# 01-POWER.net
KiCad netlist of a schematic drawn in Altium Designer
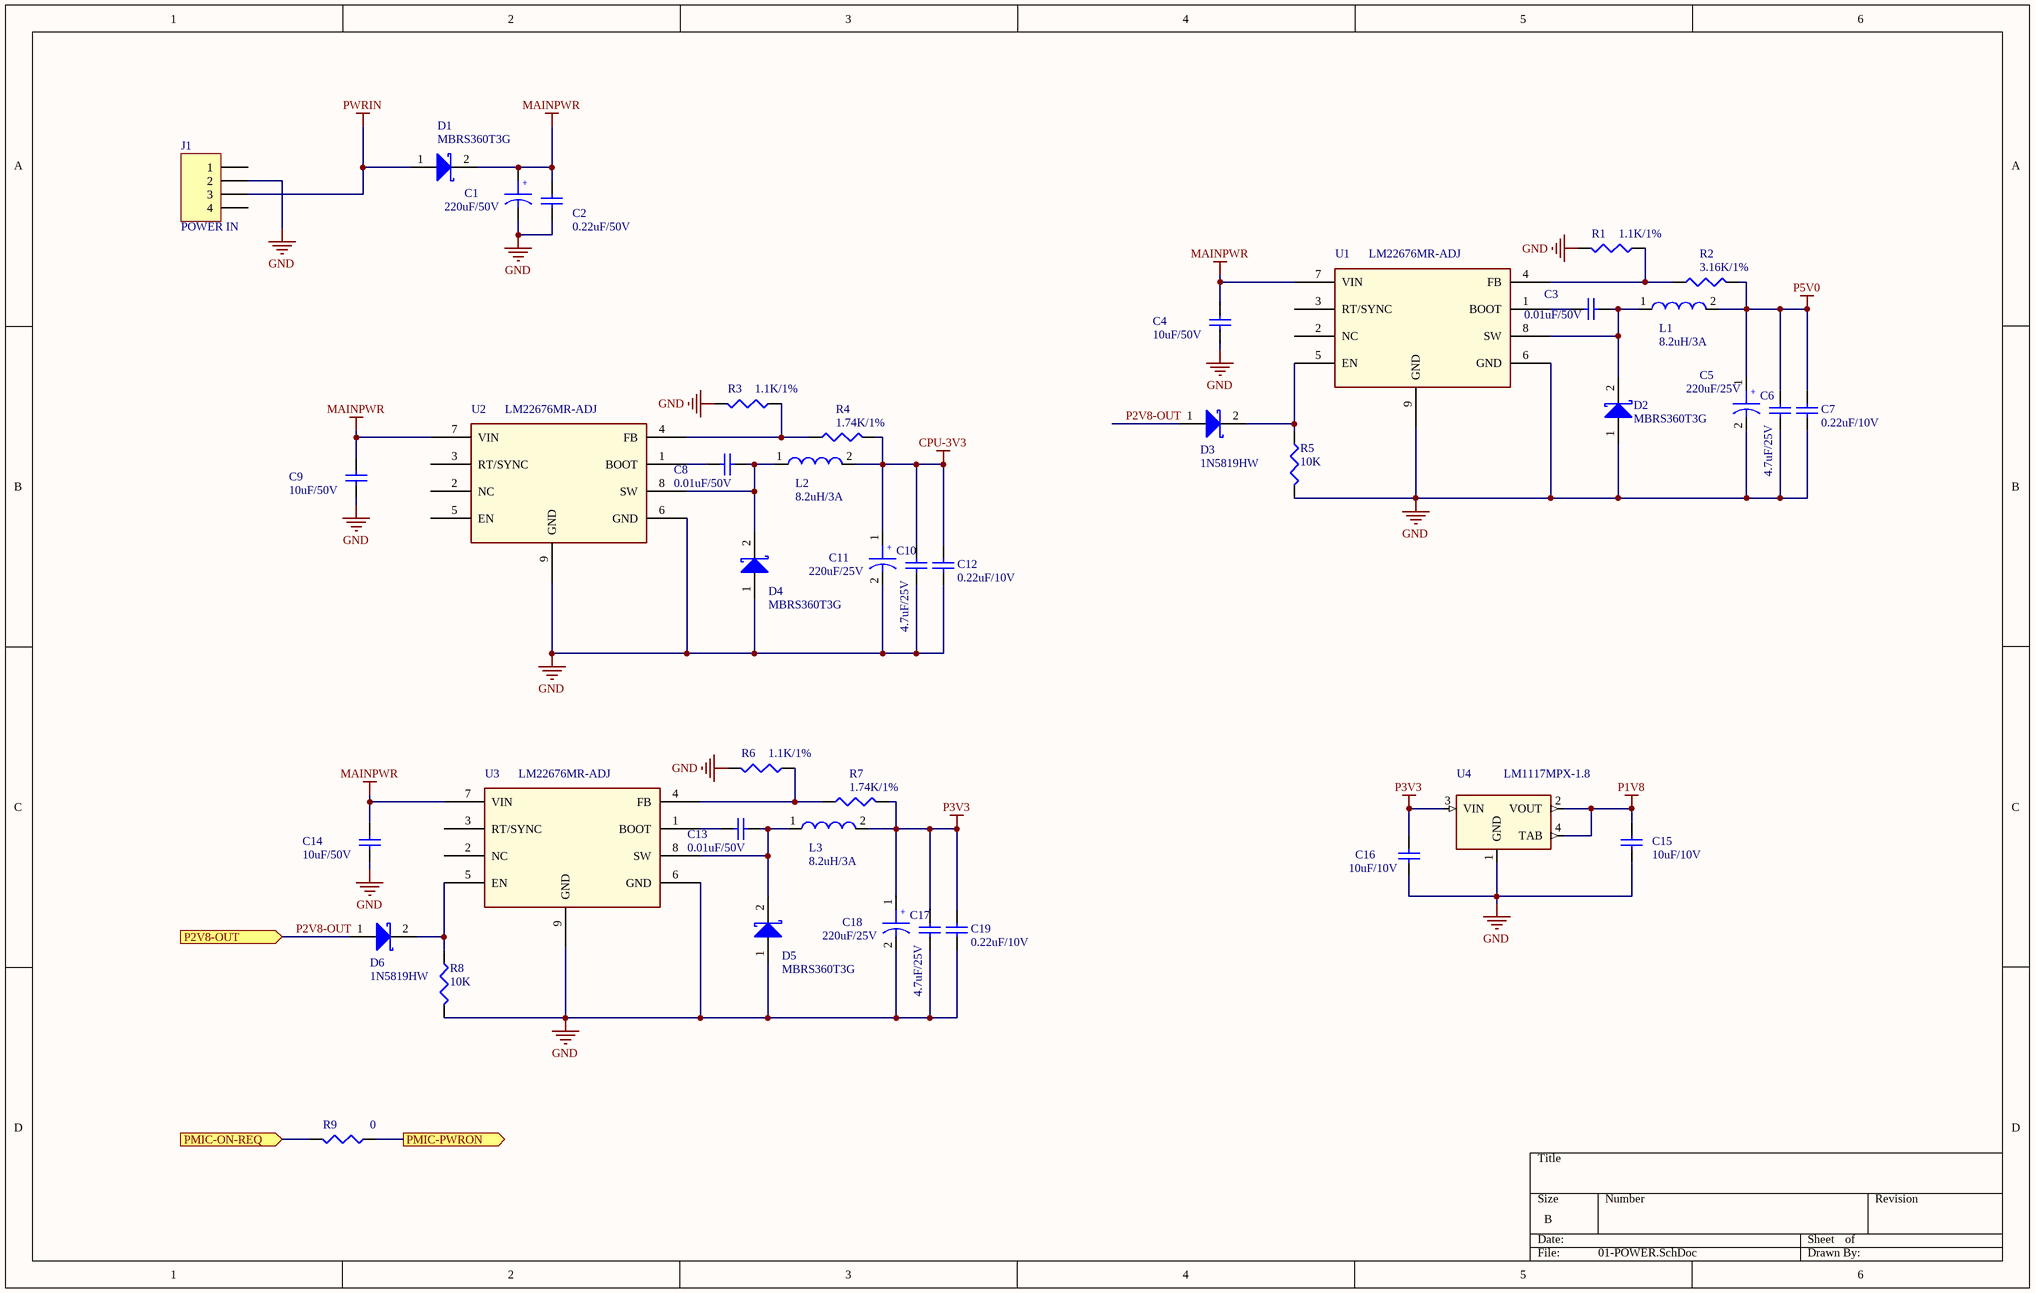
[diagram p0: 01-POWER.SchDoc]

(export (version "E")
  (design (tool "Eeschema 10.0.6"))
  (components
    (comp (ref "C1") (value "220uF/50V") (footprint "DL-10*10.5") (libsource (lib "") (part "CAP WP_1")))
    (comp (ref "C2")
      (value "0.22uF/50V")
      (footprint "0603")
      (description "Capacitor")
      (fields (field (name "PUBLISHER") "Altium Limited"))
      (libsource (lib "Miscellaneous Devices") (part "Cap"))
    )
    (comp (ref "C3")
      (value "0.01uF/50V")
      (footprint "0402")
      (description "Capacitor")
      (fields (field (name "PUBLISHER") "Altium Limited"))
      (libsource (lib "Miscellaneous Devices") (part "Cap"))
    )
    (comp (ref "C4")
      (value "10uF/50V")
      (footprint "1210")
      (description "Capacitor")
      (fields (field (name "PUBLISHER") "Altium Limited"))
      (libsource (lib "Miscellaneous Devices") (part "Cap"))
    )
    (comp (ref "C5") (value "220uF/25V") (footprint "DL-8*10.5") (libsource (lib "*") (part "CAP WP")))
    (comp (ref "C6")
      (value "4.7uF/25V")
      (footprint "0805")
      (description "Capacitor")
      (fields (field (name "PUBLISHER") "Altium Limited"))
      (libsource (lib "Miscellaneous Devices") (part "Cap"))
    )
    (comp (ref "C7")
      (value "0.22uF/10V")
      (footprint "0402")
      (description "Capacitor")
      (fields (field (name "PUBLISHER") "Altium Limited"))
      (libsource (lib "Miscellaneous Devices") (part "Cap"))
    )
    (comp (ref "C8")
      (value "0.01uF/50V")
      (footprint "0402")
      (description "Capacitor")
      (fields (field (name "PUBLISHER") "Altium Limited"))
      (libsource (lib "Miscellaneous Devices") (part "Cap"))
    )
    (comp (ref "C9")
      (value "10uF/50V")
      (footprint "1210")
      (description "Capacitor")
      (fields (field (name "PUBLISHER") "Altium Limited"))
      (libsource (lib "Miscellaneous Devices") (part "Cap"))
    )
    (comp (ref "C10")
      (value "4.7uF/25V")
      (footprint "0805")
      (description "Capacitor")
      (fields (field (name "PUBLISHER") "Altium Limited"))
      (libsource (lib "Miscellaneous Devices") (part "Cap"))
    )
    (comp (ref "C11") (value "220uF/25V") (footprint "DL-8*10.5") (libsource (lib "*") (part "CAP WP")))
    (comp (ref "C12")
      (value "0.22uF/10V")
      (footprint "0402")
      (description "Capacitor")
      (fields (field (name "PUBLISHER") "Altium Limited"))
      (libsource (lib "Miscellaneous Devices") (part "Cap"))
    )
    (comp (ref "C13")
      (value "0.01uF/50V")
      (footprint "0402")
      (description "Capacitor")
      (fields (field (name "PUBLISHER") "Altium Limited"))
      (libsource (lib "Miscellaneous Devices") (part "Cap"))
    )
    (comp (ref "C14")
      (value "10uF/50V")
      (footprint "1210")
      (description "Capacitor")
      (fields (field (name "PUBLISHER") "Altium Limited"))
      (libsource (lib "Miscellaneous Devices") (part "Cap"))
    )
    (comp (ref "C15")
      (value "10uF/10V")
      (footprint "0805")
      (description "Capacitor")
      (fields (field (name "PUBLISHER") "Altium Limited"))
      (libsource (lib "Miscellaneous Devices") (part "Cap"))
    )
    (comp (ref "C16")
      (value "10uF/10V")
      (footprint "0805")
      (description "Capacitor")
      (fields (field (name "PUBLISHER") "Altium Limited"))
      (libsource (lib "Miscellaneous Devices") (part "Cap"))
    )
    (comp (ref "C17")
      (value "4.7uF/25V")
      (footprint "0805")
      (description "Capacitor")
      (fields (field (name "PUBLISHER") "Altium Limited"))
      (libsource (lib "Miscellaneous Devices") (part "Cap"))
    )
    (comp (ref "C18") (value "220uF/25V") (footprint "DL-8*10.5") (libsource (lib "*") (part "CAP WP")))
    (comp (ref "C19")
      (value "0.22uF/10V")
      (footprint "0402")
      (description "Capacitor")
      (fields (field (name "PUBLISHER") "Altium Limited"))
      (libsource (lib "Miscellaneous Devices") (part "Cap"))
    )
    (comp (ref "D1")
      (value "MBRS360T3G")
      (footprint "SMC")
      (description "Schottky Rectifier")
      (libsource (lib "Miscellaneous Devices") (part "Diode 11DQ03"))
    )
    (comp (ref "D2")
      (value "MBRS360T3G")
      (footprint "SMC")
      (description "Schottky Rectifier")
      (libsource (lib "Miscellaneous Devices") (part "Diode 11DQ03"))
    )
    (comp (ref "D3")
      (value "1N5819HW")
      (footprint "1N5819")
      (description "Schottky Rectifier")
      (libsource (lib "Miscellaneous Devices") (part "Diode 11DQ03"))
    )
    (comp (ref "D4")
      (value "MBRS360T3G")
      (footprint "SMC")
      (description "Schottky Rectifier")
      (libsource (lib "Miscellaneous Devices") (part "Diode 11DQ03"))
    )
    (comp (ref "D5")
      (value "MBRS360T3G")
      (footprint "SMC")
      (description "Schottky Rectifier")
      (libsource (lib "Miscellaneous Devices") (part "Diode 11DQ03"))
    )
    (comp (ref "D6")
      (value "1N5819HW")
      (footprint "1N5819")
      (description "Schottky Rectifier")
      (libsource (lib "Miscellaneous Devices") (part "Diode 11DQ03"))
    )
    (comp (ref "J1")
      (value "POWER IN")
      (footprint "5557-4PIN")
      (description "Header, 4-Pin")
      (fields (field (name "PUBLISHER") "Altium Limited"))
      (libsource (lib "Miscellaneous Connectors") (part "Header 4"))
    )
    (comp (ref "L1")
      (value "8.2uH/3A")
      (footprint "IND_10X10")
      (fields (field (name "PART NUMBER") "SH00000AJ00"))
      (libsource (lib "*") (part "4.7UH_CDH2D09BNP-4R7MC_0.7A_20%"))
    )
    (comp (ref "L2")
      (value "8.2uH/3A")
      (footprint "IND_10X10")
      (fields (field (name "PART NUMBER") "SH00000AJ00"))
      (libsource (lib "*") (part "4.7UH_CDH2D09BNP-4R7MC_0.7A_20%"))
    )
    (comp (ref "L3")
      (value "8.2uH/3A")
      (footprint "IND_10X10")
      (fields (field (name "PART NUMBER") "SH00000AJ00"))
      (libsource (lib "*") (part "4.7UH_CDH2D09BNP-4R7MC_0.7A_20%"))
    )
    (comp (ref "R1")
      (value "1.1K/1%")
      (footprint "0402")
      (description "Resistor")
      (fields (field (name "PUBLISHER") "Altium Limited"))
      (libsource (lib "Miscellaneous Devices") (part "Res3"))
    )
    (comp (ref "R2")
      (value "3.16K/1%")
      (footprint "0402")
      (description "Resistor")
      (fields (field (name "PUBLISHER") "Altium Limited"))
      (libsource (lib "Miscellaneous Devices") (part "Res3"))
    )
    (comp (ref "R3")
      (value "1.1K/1%")
      (footprint "0402")
      (description "Resistor")
      (fields (field (name "PUBLISHER") "Altium Limited"))
      (libsource (lib "Miscellaneous Devices") (part "Res3"))
    )
    (comp (ref "R4")
      (value "1.74K/1%")
      (footprint "0402")
      (description "Resistor")
      (fields (field (name "PUBLISHER") "Altium Limited"))
      (libsource (lib "Miscellaneous Devices") (part "Res3"))
    )
    (comp (ref "R5")
      (value "10K")
      (footprint "0402")
      (description "Resistor")
      (fields (field (name "PUBLISHER") "Altium Limited"))
      (libsource (lib "Miscellaneous Devices") (part "Res3"))
    )
    (comp (ref "R6")
      (value "1.1K/1%")
      (footprint "0402")
      (description "Resistor")
      (fields (field (name "PUBLISHER") "Altium Limited"))
      (libsource (lib "Miscellaneous Devices") (part "Res3"))
    )
    (comp (ref "R7")
      (value "1.74K/1%")
      (footprint "0402")
      (description "Resistor")
      (fields (field (name "PUBLISHER") "Altium Limited"))
      (libsource (lib "Miscellaneous Devices") (part "Res3"))
    )
    (comp (ref "R8")
      (value "10K")
      (footprint "0402")
      (description "Resistor")
      (fields (field (name "PUBLISHER") "Altium Limited"))
      (libsource (lib "Miscellaneous Devices") (part "Res3"))
    )
    (comp (ref "R9")
      (value "0")
      (footprint "0402")
      (description "Resistor")
      (fields (field (name "PUBLISHER") "Altium Limited"))
      (libsource (lib "Miscellaneous Devices") (part "Res3"))
    )
    (comp (ref "U1") (value "LM22676MR-ADJ") (libsource (lib "*") (part "LM22670_0")))
    (comp (ref "U2") (value "LM22676MR-ADJ") (libsource (lib "*") (part "LM22670_0")))
    (comp (ref "U3") (value "LM22676MR-ADJ") (libsource (lib "*") (part "LM22670_0")))
    (comp (ref "U4")
      (value "LM1117MPX-1.8")
      (footprint "AMS1117")
      (description "IC VREG LDO 1.8V 1A 10V SOT-223")
      (libsource (lib "*") (part "LD1117AS18"))
    )
  )
  (nets
    (net (code "1") (name "/P2V8-OUT") (class "Default")
      (node (ref "D3") (pin "1") (pinfunction "A_1") (pintype "passive"))
      (node (ref "D6") (pin "1") (pinfunction "A_1") (pintype "passive"))
    )
    (net (code "2") (name "/PMIC-ON-REQ") (class "Default")
      (node (ref "R9") (pin "2") (pinfunction "2_2") (pintype "passive"))
    )
    (net (code "3") (name "/PMIC-PWRON") (class "Default")
      (node (ref "R9") (pin "1") (pinfunction "1_1") (pintype "passive"))
    )
    (net (code "4") (name "CPU-3V3") (class "Default")
      (node (ref "C10") (pin "2") (pinfunction "2_2") (pintype "passive"))
      (node (ref "C11") (pin "1") (pinfunction "1_1") (pintype "passive"))
      (node (ref "C12") (pin "2") (pinfunction "2_2") (pintype "passive"))
      (node (ref "L2") (pin "2") (pinfunction "2_2") (pintype "passive"))
      (node (ref "R4") (pin "2") (pinfunction "2_2") (pintype "passive"))
    )
    (net (code "5") (name "GND") (class "Default")
      (node (ref "C1") (pin "2") (pinfunction "2_2") (pintype "passive"))
      (node (ref "C10") (pin "1") (pinfunction "1_1") (pintype "passive"))
      (node (ref "C11") (pin "2") (pinfunction "2_2") (pintype "passive"))
      (node (ref "C12") (pin "1") (pinfunction "1_1") (pintype "passive"))
      (node (ref "C14") (pin "2") (pinfunction "2_2") (pintype "passive"))
      (node (ref "C15") (pin "2") (pinfunction "2_2") (pintype "passive"))
      (node (ref "C16") (pin "2") (pinfunction "2_2") (pintype "passive"))
      (node (ref "C17") (pin "1") (pinfunction "1_1") (pintype "passive"))
      (node (ref "C18") (pin "2") (pinfunction "2_2") (pintype "passive"))
      (node (ref "C19") (pin "1") (pinfunction "1_1") (pintype "passive"))
      (node (ref "C2") (pin "2") (pinfunction "2_2") (pintype "passive"))
      (node (ref "C4") (pin "2") (pinfunction "2_2") (pintype "passive"))
      (node (ref "C5") (pin "2") (pinfunction "2_2") (pintype "passive"))
      (node (ref "C6") (pin "1") (pinfunction "1_1") (pintype "passive"))
      (node (ref "C7") (pin "1") (pinfunction "1_1") (pintype "passive"))
      (node (ref "C9") (pin "2") (pinfunction "2_2") (pintype "passive"))
      (node (ref "D2") (pin "1") (pinfunction "A_1") (pintype "passive"))
      (node (ref "D4") (pin "1") (pinfunction "A_1") (pintype "passive"))
      (node (ref "D5") (pin "1") (pinfunction "A_1") (pintype "passive"))
      (node (ref "J1") (pin "2") (pinfunction "2_2") (pintype "passive"))
      (node (ref "R1") (pin "2") (pinfunction "2_2") (pintype "passive"))
      (node (ref "R3") (pin "2") (pinfunction "2_2") (pintype "passive"))
      (node (ref "R5") (pin "2") (pinfunction "2_2") (pintype "passive"))
      (node (ref "R6") (pin "2") (pinfunction "2_2") (pintype "passive"))
      (node (ref "R8") (pin "2") (pinfunction "2_2") (pintype "passive"))
      (node (ref "U1") (pin "6") (pinfunction "GND_6") (pintype "passive"))
      (node (ref "U1") (pin "9") (pinfunction "GND_9") (pintype "power_in"))
      (node (ref "U2") (pin "6") (pinfunction "GND_6") (pintype "passive"))
      (node (ref "U2") (pin "9") (pinfunction "GND_9") (pintype "power_in"))
      (node (ref "U3") (pin "6") (pinfunction "GND_6") (pintype "passive"))
      (node (ref "U3") (pin "9") (pinfunction "GND_9") (pintype "power_in"))
      (node (ref "U4") (pin "1") (pinfunction "GND_1") (pintype "power_in"))
    )
    (net (code "6") (name "MAINPWR") (class "Default")
      (node (ref "C1") (pin "1") (pinfunction "1_1") (pintype "passive"))
      (node (ref "C14") (pin "1") (pinfunction "1_1") (pintype "passive"))
      (node (ref "C2") (pin "1") (pinfunction "1_1") (pintype "passive"))
      (node (ref "C4") (pin "1") (pinfunction "1_1") (pintype "passive"))
      (node (ref "C9") (pin "1") (pinfunction "1_1") (pintype "passive"))
      (node (ref "D1") (pin "2") (pinfunction "K_2") (pintype "passive"))
      (node (ref "U1") (pin "7") (pinfunction "VIN_7") (pintype "power_in"))
      (node (ref "U2") (pin "7") (pinfunction "VIN_7") (pintype "power_in"))
      (node (ref "U3") (pin "7") (pinfunction "VIN_7") (pintype "power_in"))
    )
    (net (code "7") (name "Net-(D2-K)") (class "Default")
      (node (ref "C3") (pin "1") (pinfunction "1_1") (pintype "passive"))
      (node (ref "D2") (pin "2") (pinfunction "K_2") (pintype "passive"))
      (node (ref "L1") (pin "1") (pinfunction "1_1") (pintype "passive"))
      (node (ref "U1") (pin "8") (pinfunction "SW_8") (pintype "passive"))
    )
    (net (code "8") (name "Net-(D3-K)") (class "Default")
      (node (ref "D3") (pin "2") (pinfunction "K_2") (pintype "passive"))
      (node (ref "R5") (pin "1") (pinfunction "1_1") (pintype "passive"))
      (node (ref "U1") (pin "5") (pinfunction "EN_5") (pintype "passive"))
    )
    (net (code "9") (name "Net-(D4-K)") (class "Default")
      (node (ref "C8") (pin "1") (pinfunction "1_1") (pintype "passive"))
      (node (ref "D4") (pin "2") (pinfunction "K_2") (pintype "passive"))
      (node (ref "L2") (pin "1") (pinfunction "1_1") (pintype "passive"))
      (node (ref "U2") (pin "8") (pinfunction "SW_8") (pintype "passive"))
    )
    (net (code "10") (name "Net-(D5-K)") (class "Default")
      (node (ref "C13") (pin "1") (pinfunction "1_1") (pintype "passive"))
      (node (ref "D5") (pin "2") (pinfunction "K_2") (pintype "passive"))
      (node (ref "L3") (pin "1") (pinfunction "1_1") (pintype "passive"))
      (node (ref "U3") (pin "8") (pinfunction "SW_8") (pintype "passive"))
    )
    (net (code "11") (name "Net-(D6-K)") (class "Default")
      (node (ref "D6") (pin "2") (pinfunction "K_2") (pintype "passive"))
      (node (ref "R8") (pin "1") (pinfunction "1_1") (pintype "passive"))
      (node (ref "U3") (pin "5") (pinfunction "EN_5") (pintype "passive"))
    )
    (net (code "12") (name "Net-(U1-BOOT)") (class "Default")
      (node (ref "C3") (pin "2") (pinfunction "2_2") (pintype "passive"))
      (node (ref "U1") (pin "1") (pinfunction "BOOT_1") (pintype "passive"))
    )
    (net (code "13") (name "Net-(U1-FB)") (class "Default")
      (node (ref "R1") (pin "1") (pinfunction "1_1") (pintype "passive"))
      (node (ref "R2") (pin "1") (pinfunction "1_1") (pintype "passive"))
      (node (ref "U1") (pin "4") (pinfunction "FB_4") (pintype "passive"))
    )
    (net (code "14") (name "Net-(U2-BOOT)") (class "Default")
      (node (ref "C8") (pin "2") (pinfunction "2_2") (pintype "passive"))
      (node (ref "U2") (pin "1") (pinfunction "BOOT_1") (pintype "passive"))
    )
    (net (code "15") (name "Net-(U2-FB)") (class "Default")
      (node (ref "R3") (pin "1") (pinfunction "1_1") (pintype "passive"))
      (node (ref "R4") (pin "1") (pinfunction "1_1") (pintype "passive"))
      (node (ref "U2") (pin "4") (pinfunction "FB_4") (pintype "passive"))
    )
    (net (code "16") (name "Net-(U3-BOOT)") (class "Default")
      (node (ref "C13") (pin "2") (pinfunction "2_2") (pintype "passive"))
      (node (ref "U3") (pin "1") (pinfunction "BOOT_1") (pintype "passive"))
    )
    (net (code "17") (name "Net-(U3-FB)") (class "Default")
      (node (ref "R6") (pin "1") (pinfunction "1_1") (pintype "passive"))
      (node (ref "R7") (pin "1") (pinfunction "1_1") (pintype "passive"))
      (node (ref "U3") (pin "4") (pinfunction "FB_4") (pintype "passive"))
    )
    (net (code "18") (name "P1V8") (class "Default")
      (node (ref "C15") (pin "1") (pinfunction "1_1") (pintype "passive"))
      (node (ref "U4") (pin "2") (pinfunction "VOUT_2") (pintype "output"))
      (node (ref "U4") (pin "4") (pinfunction "TAB_4") (pintype "output"))
    )
    (net (code "19") (name "P3V3") (class "Default")
      (node (ref "C16") (pin "1") (pinfunction "1_1") (pintype "passive"))
      (node (ref "C17") (pin "2") (pinfunction "2_2") (pintype "passive"))
      (node (ref "C18") (pin "1") (pinfunction "1_1") (pintype "passive"))
      (node (ref "C19") (pin "2") (pinfunction "2_2") (pintype "passive"))
      (node (ref "L3") (pin "2") (pinfunction "2_2") (pintype "passive"))
      (node (ref "R7") (pin "2") (pinfunction "2_2") (pintype "passive"))
      (node (ref "U4") (pin "3") (pinfunction "VIN_3") (pintype "input"))
    )
    (net (code "20") (name "P5V0") (class "Default")
      (node (ref "C5") (pin "1") (pinfunction "1_1") (pintype "passive"))
      (node (ref "C6") (pin "2") (pinfunction "2_2") (pintype "passive"))
      (node (ref "C7") (pin "2") (pinfunction "2_2") (pintype "passive"))
      (node (ref "L1") (pin "2") (pinfunction "2_2") (pintype "passive"))
      (node (ref "R2") (pin "2") (pinfunction "2_2") (pintype "passive"))
    )
    (net (code "21") (name "PWRIN") (class "Default")
      (node (ref "D1") (pin "1") (pinfunction "A_1") (pintype "passive"))
      (node (ref "J1") (pin "3") (pinfunction "3_3") (pintype "passive"))
    )
    (net (code "22") (name "unconnected-(J1-Pad1)") (class "Default")
      (node (ref "J1") (pin "1") (pinfunction "1_1") (pintype "passive"))
    )
    (net (code "23") (name "unconnected-(J1-Pad4)") (class "Default")
      (node (ref "J1") (pin "4") (pinfunction "4_4") (pintype "passive"))
    )
    (net (code "24") (name "unconnected-(U1-NC-Pad2)") (class "Default")
      (node (ref "U1") (pin "2") (pinfunction "NC_2") (pintype "passive"))
    )
    (net (code "25") (name "unconnected-(U1-RT{slash}SYNC-Pad3)") (class "Default")
      (node (ref "U1") (pin "3") (pinfunction "RT/SYNC_3") (pintype "passive"))
    )
    (net (code "26") (name "unconnected-(U2-EN-Pad5)") (class "Default")
      (node (ref "U2") (pin "5") (pinfunction "EN_5") (pintype "passive"))
    )
    (net (code "27") (name "unconnected-(U2-NC-Pad2)") (class "Default")
      (node (ref "U2") (pin "2") (pinfunction "NC_2") (pintype "passive"))
    )
    (net (code "28") (name "unconnected-(U2-RT{slash}SYNC-Pad3)") (class "Default")
      (node (ref "U2") (pin "3") (pinfunction "RT/SYNC_3") (pintype "passive"))
    )
    (net (code "29") (name "unconnected-(U3-NC-Pad2)") (class "Default")
      (node (ref "U3") (pin "2") (pinfunction "NC_2") (pintype "passive"))
    )
    (net (code "30") (name "unconnected-(U3-RT{slash}SYNC-Pad3)") (class "Default")
      (node (ref "U3") (pin "3") (pinfunction "RT/SYNC_3") (pintype "passive"))
    )
  )
)
